# MagicWandFinal.net
KiCad netlist of a schematic drawn in Altium Designer
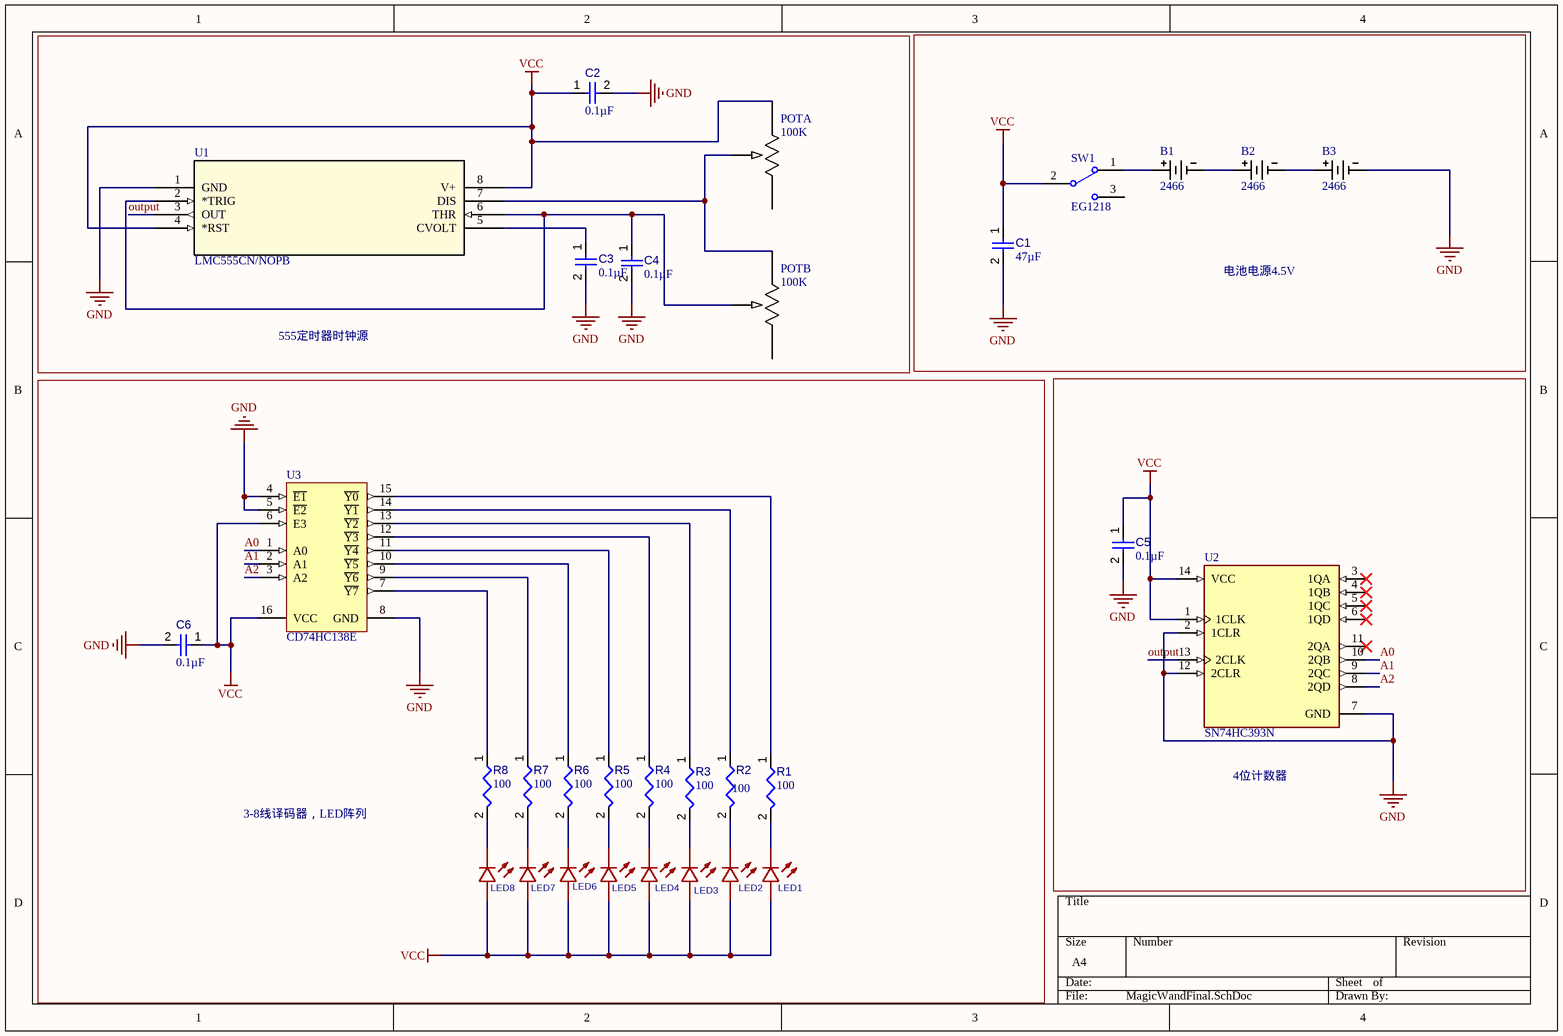
[diagram p0: MagicWandFinal.SchDoc]

(export (version "E")
  (design (tool "Eeschema 10.0.6"))
  (components
    (comp (ref "B1")
      (value "2466")
      (footprint "2466_KEY")
      (description "Description")
      (fields (field (name "COPYRIGHT") "Copyright (C) 2025 Ultra Librarian. All rights reserved."))
      (libsource (lib "AAA电池底座（keystone_2466)") (part "2466"))
    )
    (comp (ref "B2")
      (value "2466")
      (footprint "2466_KEY")
      (description "Description")
      (fields (field (name "COPYRIGHT") "Copyright (C) 2025 Ultra Librarian. All rights reserved."))
      (libsource (lib "AAA电池底座（keystone_2466)") (part "2466"))
    )
    (comp (ref "B3")
      (value "2466")
      (footprint "2466_KEY")
      (description "Description")
      (fields (field (name "COPYRIGHT") "Copyright (C) 2025 Ultra Librarian. All rights reserved."))
      (libsource (lib "AAA电池底座（keystone_2466)") (part "2466"))
    )
    (comp (ref "C1")
      (value "47µF")
      (footprint "CAPC0805(2012)145_L")
      (description "Chip Capacitor, 47µF +/-40%, 6.3V, 0805, Thickness 1.45 mm")
      (fields (field (name "TOLERANCE") "10%") (field (name "Comment") "Capacitor 47µF +/-40% 6.3V 0805"))
      (libsource (lib "新宇 付") (part "CAP-NP-2"))
    )
    (comp (ref "C2")
      (value "0.1µF")
      (footprint "CAPC0805(2012)145_L")
      (description "Chip Capacitor, 47µF +/-40%, 6.3V, 0805, Thickness 1.45 mm")
      (fields (field (name "TOLERANCE") "10%") (field (name "Comment") "Capacitor 47µF +/-40% 6.3V 0805"))
      (libsource (lib "新宇 付") (part "CAP-NP-2"))
    )
    (comp (ref "C3")
      (value "0.1µF")
      (footprint "CAPC0805(2012)145_L")
      (description "Chip Capacitor, 47µF +/-40%, 6.3V, 0805, Thickness 1.45 mm")
      (fields (field (name "TOLERANCE") "10%") (field (name "Comment") "Capacitor 47µF +/-40% 6.3V 0805"))
      (libsource (lib "新宇 付") (part "CAP-NP-2"))
    )
    (comp (ref "C4")
      (value "0.1µF")
      (footprint "CAPC0805(2012)145_L")
      (description "Chip Capacitor, 47µF +/-40%, 6.3V, 0805, Thickness 1.45 mm")
      (fields (field (name "TOLERANCE") "10%") (field (name "Comment") "Capacitor 47µF +/-40% 6.3V 0805"))
      (libsource (lib "新宇 付") (part "CAP-NP-2"))
    )
    (comp (ref "C5")
      (value "0.1µF")
      (footprint "CAPC0805(2012)145_L")
      (description "Chip Capacitor, 47µF +/-40%, 6.3V, 0805, Thickness 1.45 mm")
      (fields (field (name "TOLERANCE") "10%") (field (name "Comment") "Capacitor 47µF +/-40% 6.3V 0805"))
      (libsource (lib "新宇 付") (part "CAP-NP-2"))
    )
    (comp (ref "C6")
      (value "0.1µF")
      (footprint "CAPC0805(2012)145_L")
      (description "Chip Capacitor, 47µF +/-40%, 6.3V, 0805, Thickness 1.45 mm")
      (fields (field (name "TOLERANCE") "10%") (field (name "Comment") "Capacitor 47µF +/-40% 6.3V 0805"))
      (libsource (lib "新宇 付") (part "CAP-NP-2"))
    )
    (comp (ref "LED1")
      (value "FC-DA1608HRK-620D")
      (footprint "LED0603-RD_RED")
      (libsource (lib "C84263_发光二极管-LED_0603") (part "FC-DA1608HRK-620D"))
    )
    (comp (ref "LED2")
      (value "FC-DA1608HRK-620D")
      (footprint "LED0603-RD_RED")
      (libsource (lib "C84263_发光二极管-LED_0603") (part "FC-DA1608HRK-620D"))
    )
    (comp (ref "LED3")
      (value "FC-DA1608HRK-620D")
      (footprint "LED0603-RD_RED")
      (libsource (lib "C84263_发光二极管-LED_0603") (part "FC-DA1608HRK-620D"))
    )
    (comp (ref "LED4")
      (value "FC-DA1608HRK-620D")
      (footprint "LED0603-RD_RED")
      (libsource (lib "C84263_发光二极管-LED_0603") (part "FC-DA1608HRK-620D"))
    )
    (comp (ref "LED5")
      (value "FC-DA1608HRK-620D")
      (footprint "LED0603-RD_RED")
      (libsource (lib "C84263_发光二极管-LED_0603") (part "FC-DA1608HRK-620D"))
    )
    (comp (ref "LED6")
      (value "FC-DA1608HRK-620D")
      (footprint "LED0603-RD_RED")
      (libsource (lib "C84263_发光二极管-LED_0603") (part "FC-DA1608HRK-620D"))
    )
    (comp (ref "LED7")
      (value "FC-DA1608HRK-620D")
      (footprint "LED0603-RD_RED")
      (libsource (lib "C84263_发光二极管-LED_0603") (part "FC-DA1608HRK-620D"))
    )
    (comp (ref "LED8")
      (value "FC-DA1608HRK-620D")
      (footprint "LED0603-RD_RED")
      (libsource (lib "C84263_发光二极管-LED_0603") (part "FC-DA1608HRK-620D"))
    )
    (comp (ref "POTA")
      (value "100K")
      (footprint "POT_CT-6EP103_NDC")
      (description "Description")
      (fields
        (field (name "MANUFACTURER_PART_NUMBER") "CT-6EP103")
        (field (name "COPYRIGHT") "Copyright (C) 2026 Ultra Librarian. All rights reserved.")
      )
      (libsource (lib "CT-6EP103") (part "CT-6EP103"))
    )
    (comp (ref "POTB")
      (value "100K")
      (footprint "POT_CT-6EP103_NDC")
      (description "Description")
      (fields
        (field (name "MANUFACTURER_PART_NUMBER") "CT-6EP103")
        (field (name "COPYRIGHT") "Copyright (C) 2026 Ultra Librarian. All rights reserved.")
      )
      (libsource (lib "CT-6EP103") (part "CT-6EP103"))
    )
    (comp (ref "R1")
      (value "100")
      (footprint "RESC0402(1005)_L")
      (description "Chip Resistor, 100 Ohms, +/-1 %, 63 mW, -55 to 155 degC, 0402")
      (fields (field (name "POWER") "63mW") (field (name "TOLERANCE") "1%"))
      (libsource (lib "新宇 付") (part "RES-2"))
    )
    (comp (ref "R2")
      (value "100")
      (footprint "RESC0402(1005)_L")
      (description "Chip Resistor, 100 Ohms, +/-1 %, 63 mW, -55 to 155 degC, 0402")
      (fields (field (name "POWER") "63mW") (field (name "TOLERANCE") "1%"))
      (libsource (lib "新宇 付") (part "RES-2"))
    )
    (comp (ref "R3")
      (value "100")
      (footprint "RESC0402(1005)_L")
      (description "Chip Resistor, 100 Ohms, +/-1 %, 63 mW, -55 to 155 degC, 0402")
      (fields (field (name "POWER") "63mW") (field (name "TOLERANCE") "1%"))
      (libsource (lib "新宇 付") (part "RES-2"))
    )
    (comp (ref "R4")
      (value "100")
      (footprint "RESC0402(1005)_L")
      (description "Chip Resistor, 100 Ohms, +/-1 %, 63 mW, -55 to 155 degC, 0402")
      (fields (field (name "POWER") "63mW") (field (name "TOLERANCE") "1%"))
      (libsource (lib "新宇 付") (part "RES-2"))
    )
    (comp (ref "R5")
      (value "100")
      (footprint "RESC0402(1005)_L")
      (description "Chip Resistor, 100 Ohms, +/-1 %, 63 mW, -55 to 155 degC, 0402")
      (fields (field (name "POWER") "63mW") (field (name "TOLERANCE") "1%"))
      (libsource (lib "新宇 付") (part "RES-2"))
    )
    (comp (ref "R6")
      (value "100")
      (footprint "RESC0402(1005)_L")
      (description "Chip Resistor, 100 Ohms, +/-1 %, 63 mW, -55 to 155 degC, 0402")
      (fields (field (name "POWER") "63mW") (field (name "TOLERANCE") "1%"))
      (libsource (lib "新宇 付") (part "RES-2"))
    )
    (comp (ref "R7")
      (value "100")
      (footprint "RESC0402(1005)_L")
      (description "Chip Resistor, 100 Ohms, +/-1 %, 63 mW, -55 to 155 degC, 0402")
      (fields (field (name "POWER") "63mW") (field (name "TOLERANCE") "1%"))
      (libsource (lib "新宇 付") (part "RES-2"))
    )
    (comp (ref "R8")
      (value "100")
      (footprint "RESC0402(1005)_L")
      (description "Chip Resistor, 100 Ohms, +/-1 %, 63 mW, -55 to 155 degC, 0402")
      (fields (field (name "POWER") "63mW") (field (name "TOLERANCE") "1%"))
      (libsource (lib "新宇 付") (part "RES-2"))
    )
    (comp (ref "SW1")
      (value "EG1218")
      (footprint "ESWI-EG1218_V")
      (description "Slide Switch, 500 V, -20 to 70 degC, 3-Pin THD, RoHS")
      (libsource (lib "EG1218单刀双掷滑动开关") (part "CMP-1696-00002-1"))
    )
    (comp (ref "U1")
      (value "LMC555CN/NOPB")
      (footprint "N08E_TEX")
      (description "Worldâ€™s smallest 555 timer with low power, high accuracy and a Fmax of 3MHz 8-PDIP -40 to 85")
      (fields (field (name "COPYRIGHT") "Copyright (C) 2025 Ultra Librarian. All rights reserved."))
      (libsource (lib "LMC555CNNOPB") (part "LMC555CNNOPB"))
    )
    (comp (ref "U2")
      (value "SN74HC393N")
      (footprint "FP-N0014A-MFG")
      (description "IC DUAL 4-BIT BIN CNTR 14-DIP")
      (libsource (lib "Altium Content Vault") (part "e5eb3b22cad97e3c114da7fbb6a71ef"))
    )
    (comp (ref "U3")
      (value "CD74HC138E")
      (footprint "N0016A")
      (description "High Speed CMOS Logic 3-to-8 Line Decoder Demultiplexer Inverting and Non-Inverting, N0016A, TUBE")
      (fields
        (field (name "GENERIC PART NUMBER") "CD74HC138")
        (field (name "MANUFACTURER") "Texas Instruments")
      )
      (libsource (lib "Altium Content Vault") (part "TI-CDX4HCT138-16"))
    )
  )
  (nets
    (net (code "1") (name "/A0") (class "Default")
      (node (ref "U2") (pin "10") (pinfunction "2QB_10") (pintype "output"))
      (node (ref "U3") (pin "1") (pinfunction "A0_1") (pintype "input"))
    )
    (net (code "2") (name "/A1") (class "Default")
      (node (ref "U2") (pin "9") (pinfunction "2QC_9") (pintype "output"))
      (node (ref "U3") (pin "2") (pinfunction "A1_2") (pintype "input"))
    )
    (net (code "3") (name "/A2") (class "Default")
      (node (ref "U2") (pin "8") (pinfunction "2QD_8") (pintype "output"))
      (node (ref "U3") (pin "3") (pinfunction "A2_3") (pintype "input"))
    )
    (net (code "4") (name "/output") (class "Default")
      (node (ref "U1") (pin "3") (pinfunction "OUT_3") (pintype "output"))
      (node (ref "U2") (pin "13") (pinfunction "2CLK_13") (pintype "input"))
    )
    (net (code "5") (name "GND") (class "Default")
      (node (ref "B3") (pin "1") (pinfunction "1_1") (pintype "passive"))
      (node (ref "C1") (pin "2") (pinfunction "2_2") (pintype "passive"))
      (node (ref "C2") (pin "2") (pinfunction "2_2") (pintype "passive"))
      (node (ref "C3") (pin "2") (pinfunction "2_2") (pintype "passive"))
      (node (ref "C4") (pin "2") (pinfunction "2_2") (pintype "passive"))
      (node (ref "C5") (pin "2") (pinfunction "2_2") (pintype "passive"))
      (node (ref "C6") (pin "2") (pinfunction "2_2") (pintype "passive"))
      (node (ref "U1") (pin "1") (pinfunction "GND_1") (pintype "power_in"))
      (node (ref "U2") (pin "12") (pinfunction "2CLR_12") (pintype "input"))
      (node (ref "U2") (pin "2") (pinfunction "1CLR_2") (pintype "input"))
      (node (ref "U2") (pin "7") (pinfunction "GND_7") (pintype "power_in"))
      (node (ref "U3") (pin "4") (pinfunction "~{E1}_4") (pintype "input"))
      (node (ref "U3") (pin "5") (pinfunction "~{E2}_5") (pintype "input"))
      (node (ref "U3") (pin "8") (pinfunction "GND_8") (pintype "power_in"))
    )
    (net (code "6") (name "Net-(B1-Pad1)") (class "Default")
      (node (ref "B1") (pin "1") (pinfunction "1_1") (pintype "passive"))
      (node (ref "B2") (pin "2") (pinfunction "2_2") (pintype "passive"))
    )
    (net (code "7") (name "Net-(B1-Pad2)") (class "Default")
      (node (ref "B1") (pin "2") (pinfunction "2_2") (pintype "passive"))
      (node (ref "SW1") (pin "1") (pinfunction "1_1") (pintype "passive"))
    )
    (net (code "8") (name "Net-(B2-Pad1)") (class "Default")
      (node (ref "B2") (pin "1") (pinfunction "1_1") (pintype "passive"))
      (node (ref "B3") (pin "2") (pinfunction "2_2") (pintype "passive"))
    )
    (net (code "9") (name "Net-(LED1-K)") (class "Default")
      (node (ref "LED1") (pin "1") (pinfunction "K_1") (pintype "passive"))
      (node (ref "R1") (pin "2") (pinfunction "2_2") (pintype "passive"))
    )
    (net (code "10") (name "Net-(LED2-K)") (class "Default")
      (node (ref "LED2") (pin "1") (pinfunction "K_1") (pintype "passive"))
      (node (ref "R2") (pin "2") (pinfunction "2_2") (pintype "passive"))
    )
    (net (code "11") (name "Net-(LED3-K)") (class "Default")
      (node (ref "LED3") (pin "1") (pinfunction "K_1") (pintype "passive"))
      (node (ref "R3") (pin "2") (pinfunction "2_2") (pintype "passive"))
    )
    (net (code "12") (name "Net-(LED4-K)") (class "Default")
      (node (ref "LED4") (pin "1") (pinfunction "K_1") (pintype "passive"))
      (node (ref "R4") (pin "2") (pinfunction "2_2") (pintype "passive"))
    )
    (net (code "13") (name "Net-(LED5-K)") (class "Default")
      (node (ref "LED5") (pin "1") (pinfunction "K_1") (pintype "passive"))
      (node (ref "R5") (pin "2") (pinfunction "2_2") (pintype "passive"))
    )
    (net (code "14") (name "Net-(LED6-K)") (class "Default")
      (node (ref "LED6") (pin "1") (pinfunction "K_1") (pintype "passive"))
      (node (ref "R6") (pin "2") (pinfunction "2_2") (pintype "passive"))
    )
    (net (code "15") (name "Net-(LED7-K)") (class "Default")
      (node (ref "LED7") (pin "1") (pinfunction "K_1") (pintype "passive"))
      (node (ref "R7") (pin "2") (pinfunction "2_2") (pintype "passive"))
    )
    (net (code "16") (name "Net-(LED8-K)") (class "Default")
      (node (ref "LED8") (pin "1") (pinfunction "K_1") (pintype "passive"))
      (node (ref "R8") (pin "2") (pinfunction "2_2") (pintype "passive"))
    )
    (net (code "17") (name "Net-(U1-*TRIG)") (class "Default")
      (node (ref "C4") (pin "1") (pinfunction "1_1") (pintype "passive"))
      (node (ref "POTB") (pin "2") (pinfunction "2_2") (pintype "passive"))
      (node (ref "U1") (pin "2") (pinfunction "*TRIG_2") (pintype "input"))
      (node (ref "U1") (pin "6") (pinfunction "THR_6") (pintype "input"))
    )
    (net (code "18") (name "Net-(U1-CVOLT)") (class "Default")
      (node (ref "C3") (pin "1") (pinfunction "1_1") (pintype "passive"))
      (node (ref "U1") (pin "5") (pinfunction "CVOLT_5") (pintype "passive"))
    )
    (net (code "19") (name "Net-(U1-DIS)") (class "Default")
      (node (ref "POTA") (pin "2") (pinfunction "2_2") (pintype "passive"))
      (node (ref "POTB") (pin "3") (pinfunction "3_3") (pintype "passive"))
      (node (ref "U1") (pin "7") (pinfunction "DIS_7") (pintype "passive"))
    )
    (net (code "20") (name "Net-(U3-~{Y0})") (class "Default")
      (node (ref "R1") (pin "1") (pinfunction "1_1") (pintype "passive"))
      (node (ref "U3") (pin "15") (pinfunction "~{Y0}_15") (pintype "output"))
    )
    (net (code "21") (name "Net-(U3-~{Y1})") (class "Default")
      (node (ref "R2") (pin "1") (pinfunction "1_1") (pintype "passive"))
      (node (ref "U3") (pin "14") (pinfunction "~{Y1}_14") (pintype "output"))
    )
    (net (code "22") (name "Net-(U3-~{Y2})") (class "Default")
      (node (ref "R3") (pin "1") (pinfunction "1_1") (pintype "passive"))
      (node (ref "U3") (pin "13") (pinfunction "~{Y2}_13") (pintype "output"))
    )
    (net (code "23") (name "Net-(U3-~{Y3})") (class "Default")
      (node (ref "R4") (pin "1") (pinfunction "1_1") (pintype "passive"))
      (node (ref "U3") (pin "12") (pinfunction "~{Y3}_12") (pintype "output"))
    )
    (net (code "24") (name "Net-(U3-~{Y4})") (class "Default")
      (node (ref "R5") (pin "1") (pinfunction "1_1") (pintype "passive"))
      (node (ref "U3") (pin "11") (pinfunction "~{Y4}_11") (pintype "output"))
    )
    (net (code "25") (name "Net-(U3-~{Y5})") (class "Default")
      (node (ref "R6") (pin "1") (pinfunction "1_1") (pintype "passive"))
      (node (ref "U3") (pin "10") (pinfunction "~{Y5}_10") (pintype "output"))
    )
    (net (code "26") (name "Net-(U3-~{Y6})") (class "Default")
      (node (ref "R7") (pin "1") (pinfunction "1_1") (pintype "passive"))
      (node (ref "U3") (pin "9") (pinfunction "~{Y6}_9") (pintype "output"))
    )
    (net (code "27") (name "Net-(U3-~{Y7})") (class "Default")
      (node (ref "R8") (pin "1") (pinfunction "1_1") (pintype "passive"))
      (node (ref "U3") (pin "7") (pinfunction "~{Y7}_7") (pintype "output"))
    )
    (net (code "28") (name "VCC") (class "Default")
      (node (ref "C1") (pin "1") (pinfunction "1_1") (pintype "passive"))
      (node (ref "C2") (pin "1") (pinfunction "1_1") (pintype "passive"))
      (node (ref "C5") (pin "1") (pinfunction "1_1") (pintype "passive"))
      (node (ref "C6") (pin "1") (pinfunction "1_1") (pintype "passive"))
      (node (ref "LED1") (pin "2") (pinfunction "A_2") (pintype "passive"))
      (node (ref "LED2") (pin "2") (pinfunction "A_2") (pintype "passive"))
      (node (ref "LED3") (pin "2") (pinfunction "A_2") (pintype "passive"))
      (node (ref "LED4") (pin "2") (pinfunction "A_2") (pintype "passive"))
      (node (ref "LED5") (pin "2") (pinfunction "A_2") (pintype "passive"))
      (node (ref "LED6") (pin "2") (pinfunction "A_2") (pintype "passive"))
      (node (ref "LED7") (pin "2") (pinfunction "A_2") (pintype "passive"))
      (node (ref "LED8") (pin "2") (pinfunction "A_2") (pintype "passive"))
      (node (ref "POTA") (pin "3") (pinfunction "3_3") (pintype "passive"))
      (node (ref "SW1") (pin "2") (pinfunction "COM_2") (pintype "passive"))
      (node (ref "U1") (pin "4") (pinfunction "*RST_4") (pintype "input"))
      (node (ref "U1") (pin "8") (pinfunction "V+_8") (pintype "power_in"))
      (node (ref "U2") (pin "1") (pinfunction "1CLK_1") (pintype "input"))
      (node (ref "U2") (pin "14") (pinfunction "VCC_14") (pintype "input"))
      (node (ref "U3") (pin "16") (pinfunction "VCC_16") (pintype "power_in"))
      (node (ref "U3") (pin "6") (pinfunction "E3_6") (pintype "input"))
    )
    (net (code "29") (name "unconnected-(POTA-Pad1)") (class "Default")
      (node (ref "POTA") (pin "1") (pinfunction "1_1") (pintype "passive"))
    )
    (net (code "30") (name "unconnected-(POTB-Pad1)") (class "Default")
      (node (ref "POTB") (pin "1") (pinfunction "1_1") (pintype "passive"))
    )
    (net (code "31") (name "unconnected-(SW1-Pad3)") (class "Default")
      (node (ref "SW1") (pin "3") (pinfunction "3_3") (pintype "passive"))
    )
    (net (code "32") (name "unconnected-(U2-1QA-Pad3)") (class "Default")
      (node (ref "U2") (pin "3") (pinfunction "1QA_3") (pintype "input+no_connect"))
    )
    (net (code "33") (name "unconnected-(U2-1QB-Pad4)") (class "Default")
      (node (ref "U2") (pin "4") (pinfunction "1QB_4") (pintype "input+no_connect"))
    )
    (net (code "34") (name "unconnected-(U2-1QC-Pad5)") (class "Default")
      (node (ref "U2") (pin "5") (pinfunction "1QC_5") (pintype "input+no_connect"))
    )
    (net (code "35") (name "unconnected-(U2-1QD-Pad6)") (class "Default")
      (node (ref "U2") (pin "6") (pinfunction "1QD_6") (pintype "input+no_connect"))
    )
    (net (code "36") (name "unconnected-(U2-2QA-Pad11)") (class "Default")
      (node (ref "U2") (pin "11") (pinfunction "2QA_11") (pintype "output+no_connect"))
    )
  )
)
